# ukmarsbot-line-sensor-basic.net
KiCad netlist of a schematic drawn in EAGLE
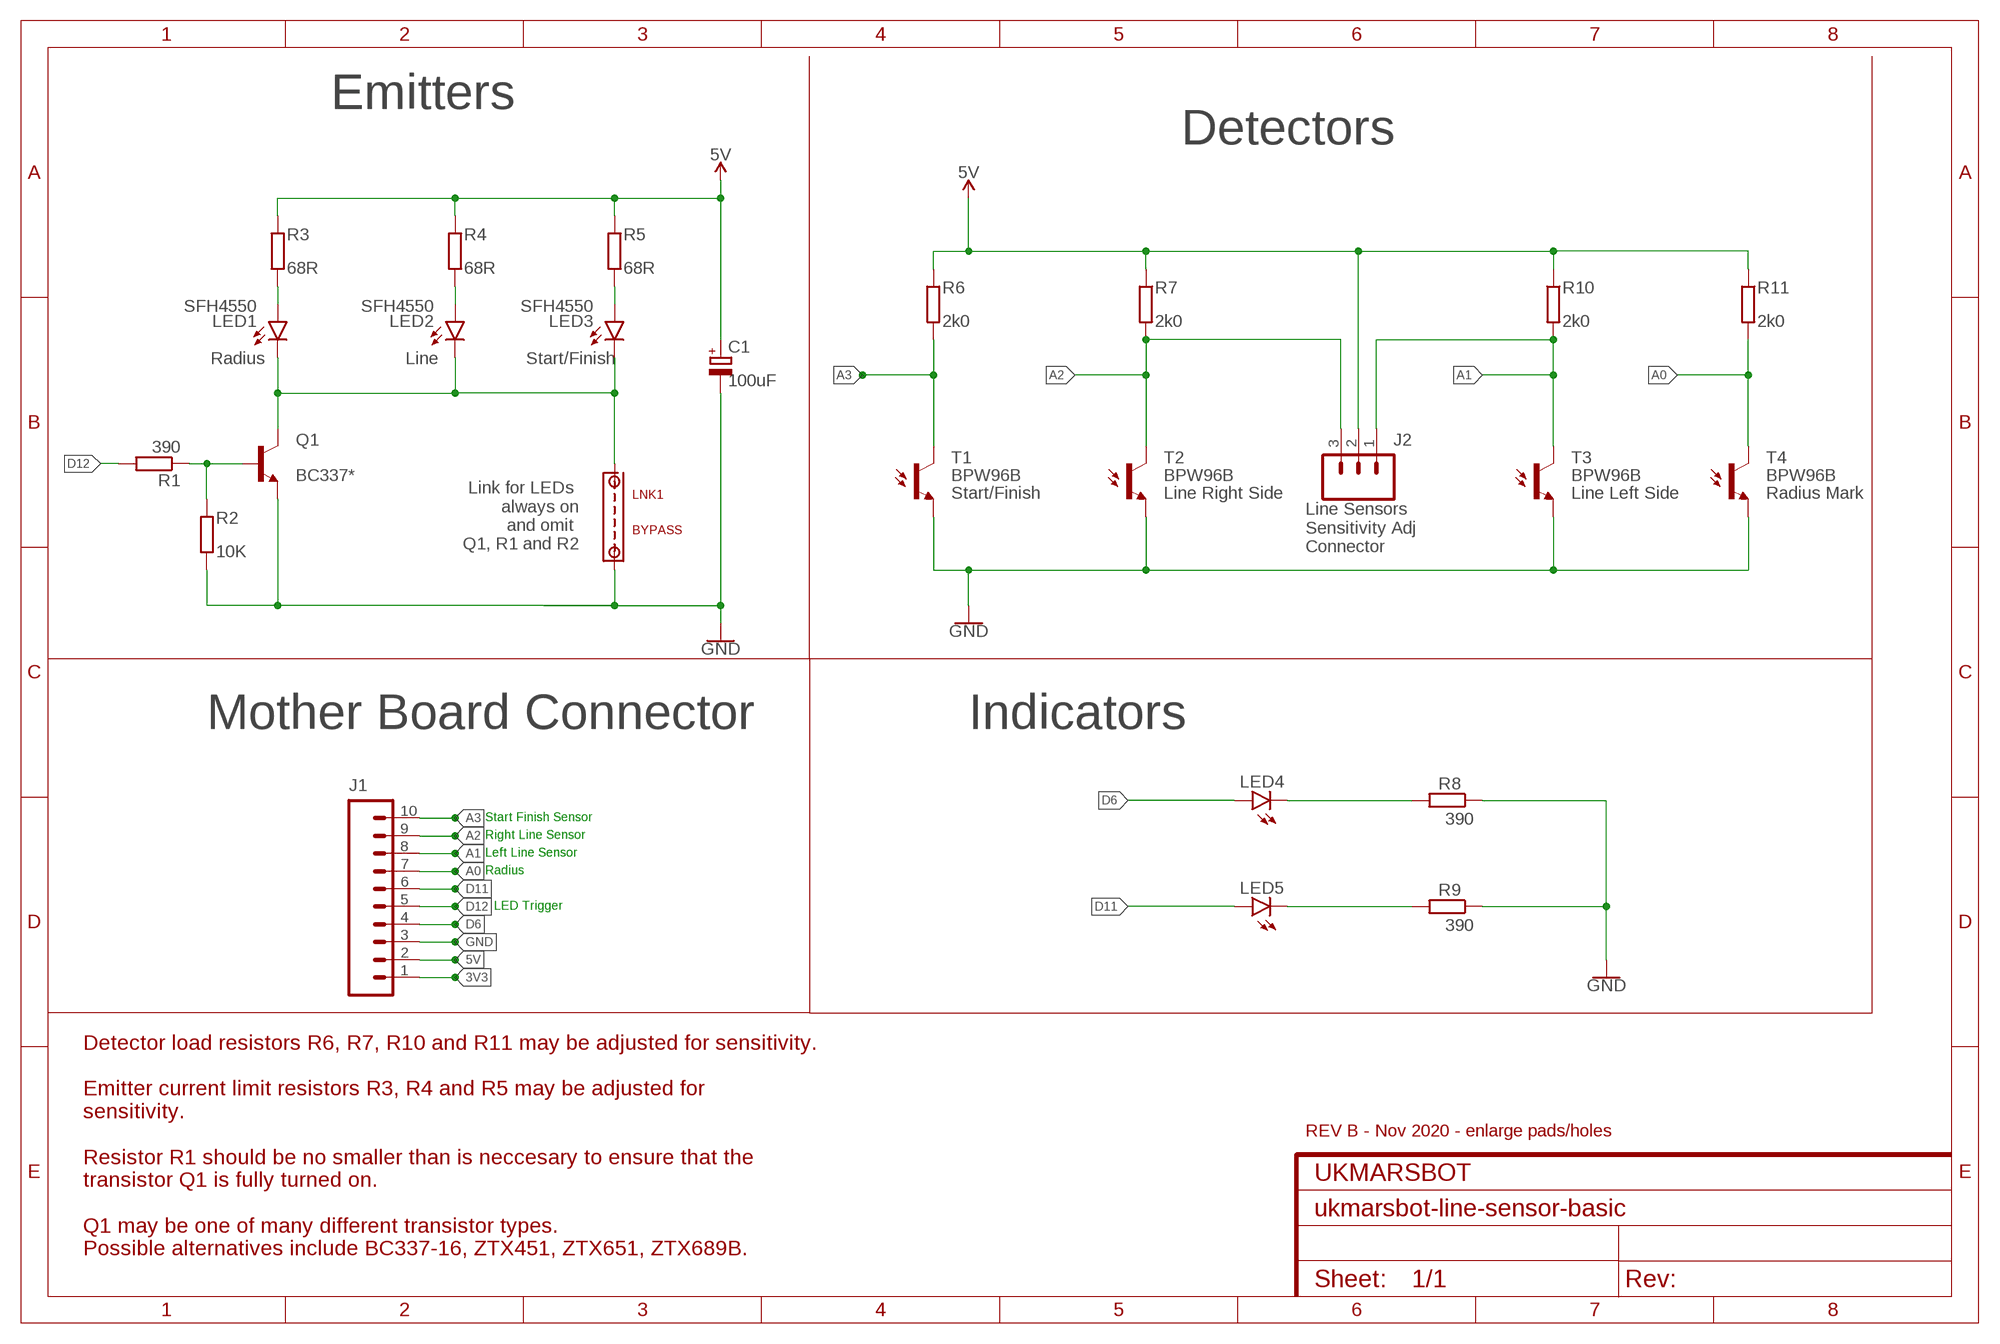
[diagram p0: schematic, sheet 1]

(export (version "E")
  (design (tool "Eeschema 10.0.6"))
  (components
    (comp (ref "C1")
      (value "100uF")
      (footprint "eagle-import:E2,5-7")
      (libsource (lib "eagle-import") (part "CPOL-EUE2.5-7"))
    )
    (comp (ref "J1")
      (value "CONN_10\"")
      (footprint "eagle-import:1X10")
      (libsource (lib "eagle-import") (part "CONN_10{dblquote}"))
    )
    (comp (ref "J2")
      (value "CONN_03")
      (footprint "eagle-import:1X03")
      (libsource (lib "eagle-import") (part "CONN_03"))
    )
    (comp (ref "LED1")
      (value "SFH4550")
      (footprint "eagle-import:LED_5MM")
      (libsource (lib "eagle-import") (part "LED5MM"))
    )
    (comp (ref "LED2")
      (value "SFH4550")
      (footprint "eagle-import:LED_5MM")
      (libsource (lib "eagle-import") (part "LED5MM"))
    )
    (comp (ref "LED3")
      (value "SFH4550")
      (footprint "eagle-import:LED_5MM")
      (libsource (lib "eagle-import") (part "LED5MM"))
    )
    (comp (ref "LED4")
      (value "LED3MM")
      (footprint "eagle-import:LED_3MM")
      (libsource (lib "eagle-import") (part "LED3MM"))
    )
    (comp (ref "LED5")
      (value "LED3MM")
      (footprint "eagle-import:LED_3MM")
      (libsource (lib "eagle-import") (part "LED3MM"))
    )
    (comp (ref "LNK1")
      (value "BYPASS")
      (footprint "eagle-import:LINK-03")
      (libsource (lib "eagle-import") (part "LINK"))
    )
    (comp (ref "Q1")
      (value "BC337*")
      (footprint "eagle-import:TO92-EBC")
      (libsource (lib "eagle-import") (part "TRANS_NPN"))
    )
    (comp (ref "R1")
      (value "390")
      (footprint "eagle-import:0207_7")
      (libsource (lib "eagle-import") (part "R-EU_0207/7"))
    )
    (comp (ref "R2")
      (value "10K")
      (footprint "eagle-import:0207_7")
      (libsource (lib "eagle-import") (part "R-EU_0207/7"))
    )
    (comp (ref "R3")
      (value "68R")
      (footprint "eagle-import:0207_7")
      (libsource (lib "eagle-import") (part "R-EU_0207/7"))
    )
    (comp (ref "R4")
      (value "68R")
      (footprint "eagle-import:0207_7")
      (libsource (lib "eagle-import") (part "R-EU_0207/7"))
    )
    (comp (ref "R5")
      (value "68R")
      (footprint "eagle-import:0207_7")
      (libsource (lib "eagle-import") (part "R-EU_0207/7"))
    )
    (comp (ref "R6")
      (value "2k0")
      (footprint "eagle-import:0207_7")
      (libsource (lib "eagle-import") (part "R-EU_0207/7"))
    )
    (comp (ref "R7")
      (value "2k0")
      (footprint "eagle-import:0207_7")
      (libsource (lib "eagle-import") (part "R-EU_0207/7"))
    )
    (comp (ref "R8")
      (value "390")
      (footprint "eagle-import:0207_7")
      (libsource (lib "eagle-import") (part "R-EU_0207/7"))
    )
    (comp (ref "R9")
      (value "390")
      (footprint "eagle-import:0207_7")
      (libsource (lib "eagle-import") (part "R-EU_0207/7"))
    )
    (comp (ref "R10")
      (value "2k0")
      (footprint "eagle-import:0207_7")
      (libsource (lib "eagle-import") (part "R-EU_0207/7"))
    )
    (comp (ref "R11")
      (value "2k0")
      (footprint "eagle-import:0207_7")
      (libsource (lib "eagle-import") (part "R-EU_0207/7"))
    )
    (comp (ref "T1")
      (value "BPW96B")
      (footprint "eagle-import:PHOTOTRANSISTOR_5MM")
      (libsource (lib "eagle-import") (part "PHOTOTRANSISTOR5MM"))
    )
    (comp (ref "T2")
      (value "BPW96B")
      (footprint "eagle-import:PHOTOTRANSISTOR_5MM")
      (libsource (lib "eagle-import") (part "PHOTOTRANSISTOR5MM"))
    )
    (comp (ref "T3")
      (value "BPW96B")
      (footprint "eagle-import:PHOTOTRANSISTOR_5MM")
      (libsource (lib "eagle-import") (part "PHOTOTRANSISTOR5MM"))
    )
    (comp (ref "T4")
      (value "BPW96B")
      (footprint "eagle-import:PHOTOTRANSISTOR_5MM")
      (libsource (lib "eagle-import") (part "PHOTOTRANSISTOR5MM"))
    )
  )
  (nets
    (net (code "1") (name "3V3") (class "Default")
      (node (ref "J1") (pin "1") (pinfunction "1_1") (pintype "passive"))
    )
    (net (code "2") (name "5V") (class "Default")
      (node (ref "C1") (pin "+") (pinfunction "+_+") (pintype "passive"))
      (node (ref "J1") (pin "2") (pinfunction "2_2") (pintype "passive"))
      (node (ref "J2") (pin "2") (pinfunction "2_2") (pintype "passive"))
      (node (ref "R10") (pin "1") (pinfunction "1_1") (pintype "passive"))
      (node (ref "R11") (pin "1") (pinfunction "1_1") (pintype "passive"))
      (node (ref "R3") (pin "2") (pinfunction "2_2") (pintype "passive"))
      (node (ref "R4") (pin "2") (pinfunction "2_2") (pintype "passive"))
      (node (ref "R5") (pin "2") (pinfunction "2_2") (pintype "passive"))
      (node (ref "R6") (pin "1") (pinfunction "1_1") (pintype "passive"))
      (node (ref "R7") (pin "1") (pinfunction "1_1") (pintype "passive"))
    )
    (net (code "3") (name "A0") (class "Default")
      (node (ref "J1") (pin "7") (pinfunction "7_7") (pintype "passive"))
      (node (ref "R11") (pin "2") (pinfunction "2_2") (pintype "passive"))
      (node (ref "T4") (pin "C") (pinfunction "C_C") (pintype "passive"))
    )
    (net (code "4") (name "A1") (class "Default")
      (node (ref "J1") (pin "8") (pinfunction "8_8") (pintype "passive"))
      (node (ref "J2") (pin "1") (pinfunction "1_1") (pintype "passive"))
      (node (ref "R10") (pin "2") (pinfunction "2_2") (pintype "passive"))
      (node (ref "T3") (pin "C") (pinfunction "C_C") (pintype "passive"))
    )
    (net (code "5") (name "A2") (class "Default")
      (node (ref "J1") (pin "9") (pinfunction "9_9") (pintype "passive"))
      (node (ref "J2") (pin "3") (pinfunction "3_3") (pintype "passive"))
      (node (ref "R7") (pin "2") (pinfunction "2_2") (pintype "passive"))
      (node (ref "T2") (pin "C") (pinfunction "C_C") (pintype "passive"))
    )
    (net (code "6") (name "A3") (class "Default")
      (node (ref "J1") (pin "10") (pinfunction "10_10") (pintype "passive"))
      (node (ref "R6") (pin "2") (pinfunction "2_2") (pintype "passive"))
      (node (ref "T1") (pin "C") (pinfunction "C_C") (pintype "passive"))
    )
    (net (code "7") (name "D6") (class "Default")
      (node (ref "J1") (pin "4") (pinfunction "4_4") (pintype "passive"))
      (node (ref "LED4") (pin "A") (pinfunction "A_A") (pintype "passive"))
    )
    (net (code "8") (name "D11") (class "Default")
      (node (ref "J1") (pin "6") (pinfunction "6_6") (pintype "passive"))
      (node (ref "LED5") (pin "A") (pinfunction "A_A") (pintype "passive"))
    )
    (net (code "9") (name "D12") (class "Default")
      (node (ref "J1") (pin "5") (pinfunction "5_5") (pintype "passive"))
      (node (ref "R1") (pin "2") (pinfunction "2_2") (pintype "passive"))
    )
    (net (code "10") (name "GND") (class "Default")
      (node (ref "C1") (pin "-") (pinfunction "-_-") (pintype "passive"))
      (node (ref "J1") (pin "3") (pinfunction "3_3") (pintype "passive"))
      (node (ref "LNK1") (pin "2") (pinfunction "2_2") (pintype "passive"))
      (node (ref "Q1") (pin "E") (pinfunction "E_E") (pintype "passive"))
      (node (ref "R2") (pin "1") (pinfunction "1_1") (pintype "passive"))
      (node (ref "R8") (pin "1") (pinfunction "1_1") (pintype "passive"))
      (node (ref "R9") (pin "1") (pinfunction "1_1") (pintype "passive"))
      (node (ref "T1") (pin "E") (pinfunction "E_E") (pintype "passive"))
      (node (ref "T2") (pin "E") (pinfunction "E_E") (pintype "passive"))
      (node (ref "T3") (pin "E") (pinfunction "E_E") (pintype "passive"))
      (node (ref "T4") (pin "E") (pinfunction "E_E") (pintype "passive"))
    )
    (net (code "11") (name "Net-(LED1-C)") (class "Default")
      (node (ref "LED1") (pin "K") (pinfunction "C_K") (pintype "passive"))
      (node (ref "LED2") (pin "K") (pinfunction "C_K") (pintype "passive"))
      (node (ref "LED3") (pin "K") (pinfunction "C_K") (pintype "passive"))
      (node (ref "LNK1") (pin "1") (pinfunction "1_1") (pintype "passive"))
      (node (ref "Q1") (pin "C") (pinfunction "C_C") (pintype "passive"))
    )
    (net (code "12") (name "Net-(LED1-PadA)") (class "Default")
      (node (ref "LED1") (pin "A") (pinfunction "A_A") (pintype "passive"))
      (node (ref "R3") (pin "1") (pinfunction "1_1") (pintype "passive"))
    )
    (net (code "13") (name "Net-(LED2-PadA)") (class "Default")
      (node (ref "LED2") (pin "A") (pinfunction "A_A") (pintype "passive"))
      (node (ref "R4") (pin "1") (pinfunction "1_1") (pintype "passive"))
    )
    (net (code "14") (name "Net-(LED3-PadA)") (class "Default")
      (node (ref "LED3") (pin "A") (pinfunction "A_A") (pintype "passive"))
      (node (ref "R5") (pin "1") (pinfunction "1_1") (pintype "passive"))
    )
    (net (code "15") (name "Net-(LED4-C)") (class "Default")
      (node (ref "LED4") (pin "K") (pinfunction "C_K") (pintype "passive"))
      (node (ref "R8") (pin "2") (pinfunction "2_2") (pintype "passive"))
    )
    (net (code "16") (name "Net-(LED5-C)") (class "Default")
      (node (ref "LED5") (pin "K") (pinfunction "C_K") (pintype "passive"))
      (node (ref "R9") (pin "2") (pinfunction "2_2") (pintype "passive"))
    )
    (net (code "17") (name "Net-(Q1-PadB)") (class "Default")
      (node (ref "Q1") (pin "B") (pinfunction "B_B") (pintype "passive"))
      (node (ref "R1") (pin "1") (pinfunction "1_1") (pintype "passive"))
      (node (ref "R2") (pin "2") (pinfunction "2_2") (pintype "passive"))
    )
  )
)
